# RG_Matrix_Driver.net
KiCad netlist of a schematic drawn in EAGLE
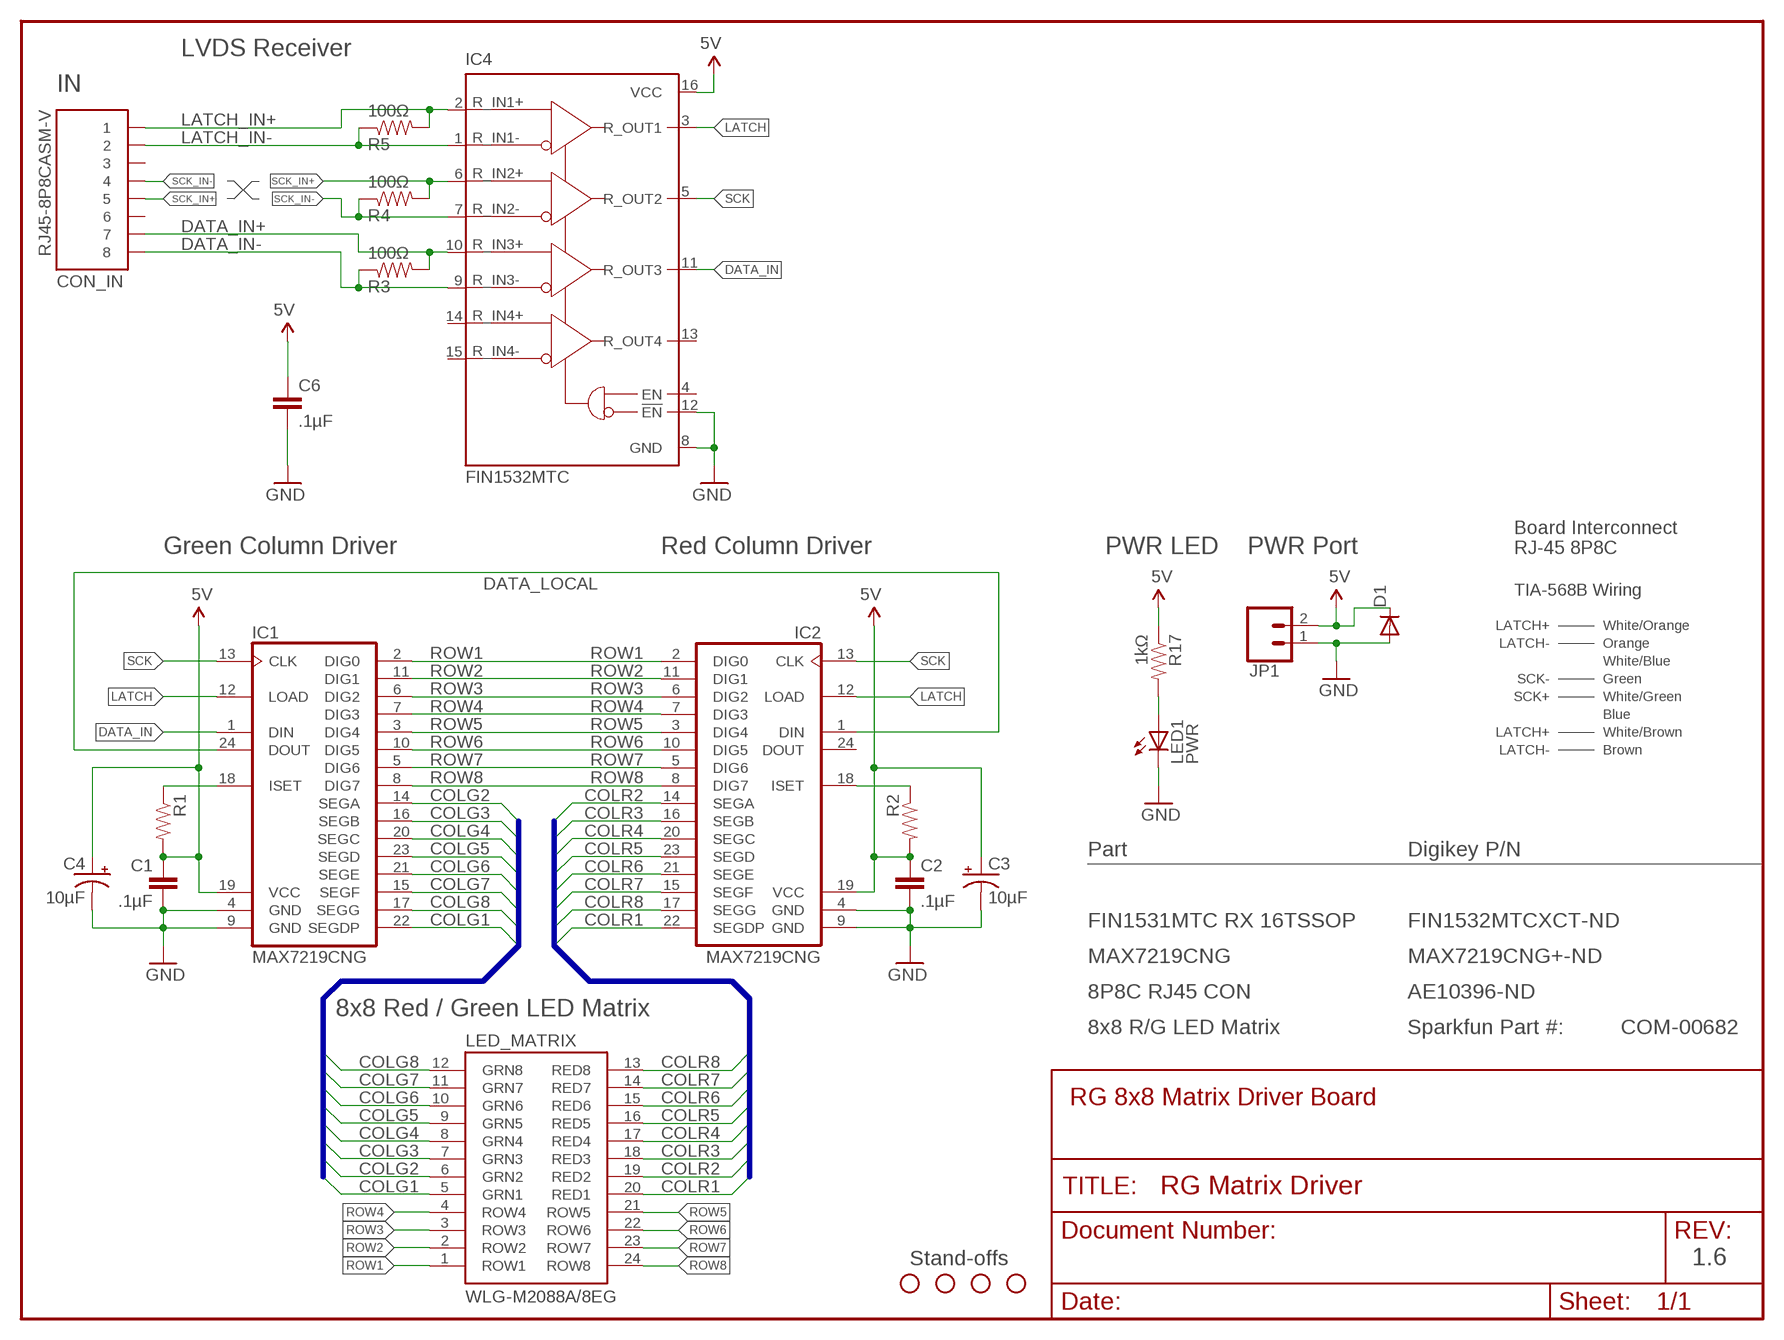
[diagram p0: schematic, sheet 1]

(export (version "E")
  (design (tool "Eeschema 10.0.6"))
  (components
    (comp (ref "C1")
      (value ".1µF")
      (footprint "eagle-import:1206")
      (libsource (lib "eagle-import") (part "CAP1206"))
    )
    (comp (ref "C2")
      (value ".1µF")
      (footprint "eagle-import:1206")
      (libsource (lib "eagle-import") (part "CAP1206"))
    )
    (comp (ref "C3")
      (value "10µF")
      (footprint "eagle-import:CPOL-RADIAL-10UF-25V")
      (libsource (lib "eagle-import") (part "CAP_POLPTH2"))
    )
    (comp (ref "C4")
      (value "10µF")
      (footprint "eagle-import:CPOL-RADIAL-10UF-25V")
      (libsource (lib "eagle-import") (part "CAP_POLPTH2"))
    )
    (comp (ref "C6")
      (value ".1µF")
      (footprint "eagle-import:1206")
      (libsource (lib "eagle-import") (part "CAP1206"))
    )
    (comp (ref "CON_IN")
      (value "RJ45-8P8CASM-V")
      (footprint "eagle-import:RJ45-8P8C-ASM")
      (libsource (lib "eagle-import") (part "RJ45-8P8CASM-V"))
    )
    (comp (ref "D1")
      (value "DIODEPTH")
      (footprint "eagle-import:DIODE-1N4001")
      (libsource (lib "eagle-import") (part "DIODEPTH"))
    )
    (comp (ref "IC1")
      (value "MAX7219CNG")
      (footprint "eagle-import:DIL24-3")
      (fields (field (name "MF") "MAXIM"))
      (libsource (lib "eagle-import") (part "MAX7219CNG"))
    )
    (comp (ref "IC2")
      (value "MAX7219CNG")
      (footprint "eagle-import:DIL24-3")
      (fields (field (name "MF") "MAXIM"))
      (libsource (lib "eagle-import") (part "MAX7219CNG"))
    )
    (comp (ref "IC4")
      (value "FIN1532MTC")
      (footprint "eagle-import:TSSOP-16")
      (libsource (lib "eagle-import") (part "FIN1532MTC"))
    )
    (comp (ref "JP1")
      (value "PWR")
      (footprint "eagle-import:1X02_PC_SMD")
      (libsource (lib "eagle-import") (part "M02"))
    )
    (comp (ref "JP3")
      (value "STAND-OFF")
      (footprint "eagle-import:STAND-OFF")
      (libsource (lib "eagle-import") (part "STAND-OFF"))
    )
    (comp (ref "JP4")
      (value "STAND-OFF")
      (footprint "eagle-import:STAND-OFF")
      (libsource (lib "eagle-import") (part "STAND-OFF"))
    )
    (comp (ref "JP5")
      (value "STAND-OFF")
      (footprint "eagle-import:STAND-OFF")
      (libsource (lib "eagle-import") (part "STAND-OFF"))
    )
    (comp (ref "JP6")
      (value "STAND-OFF")
      (footprint "eagle-import:STAND-OFF")
      (libsource (lib "eagle-import") (part "STAND-OFF"))
    )
    (comp (ref "LED1")
      (value "PWR")
      (footprint "eagle-import:LED-1206")
      (libsource (lib "eagle-import") (part "LED1206"))
    )
    (comp (ref "LED_MATRIX")
      (value "WLG-M2088A/8EG")
      (footprint "eagle-import:WLG-M2088A_8EG")
      (libsource (lib "eagle-import") (part "WLG-M2088A/8EG"))
    )
    (comp (ref "R1")
      (value "RESISTOR1206")
      (footprint "eagle-import:1206")
      (libsource (lib "eagle-import") (part "SparkFun-Resistors_RESISTOR1206"))
    )
    (comp (ref "R2")
      (value "RESISTOR1206")
      (footprint "eagle-import:1206")
      (libsource (lib "eagle-import") (part "SparkFun-Resistors_RESISTOR1206"))
    )
    (comp (ref "R3")
      (value "100Ω")
      (footprint "eagle-import:1206")
      (libsource (lib "eagle-import") (part "SparkFun-Resistors_RESISTOR1206"))
    )
    (comp (ref "R4")
      (value "100Ω")
      (footprint "eagle-import:1206")
      (libsource (lib "eagle-import") (part "SparkFun-Resistors_RESISTOR1206"))
    )
    (comp (ref "R5")
      (value "100Ω")
      (footprint "eagle-import:1206")
      (libsource (lib "eagle-import") (part "SparkFun-Resistors_RESISTOR1206"))
    )
    (comp (ref "R17")
      (value "1kΩ")
      (footprint "eagle-import:1206")
      (libsource (lib "eagle-import") (part "RESISTOR1206"))
    )
  )
  (nets
    (net (code "1") (name "/COLG1") (class "Default")
      (node (ref "IC1") (pin "22") (pinfunction "SEGDP_22") (pintype "output"))
      (node (ref "LED_MATRIX") (pin "5") (pinfunction "GRN1_5") (pintype "bidirectional"))
    )
    (net (code "2") (name "/COLG2") (class "Default")
      (node (ref "IC1") (pin "14") (pinfunction "SEGA_14") (pintype "output"))
      (node (ref "LED_MATRIX") (pin "6") (pinfunction "GRN2_6") (pintype "bidirectional"))
    )
    (net (code "3") (name "/COLG3") (class "Default")
      (node (ref "IC1") (pin "16") (pinfunction "SEGB_16") (pintype "output"))
      (node (ref "LED_MATRIX") (pin "7") (pinfunction "GRN3_7") (pintype "bidirectional"))
    )
    (net (code "4") (name "/COLG4") (class "Default")
      (node (ref "IC1") (pin "20") (pinfunction "SEGC_20") (pintype "output"))
      (node (ref "LED_MATRIX") (pin "8") (pinfunction "GRN4_8") (pintype "bidirectional"))
    )
    (net (code "5") (name "/COLG5") (class "Default")
      (node (ref "IC1") (pin "23") (pinfunction "SEGD_23") (pintype "output"))
      (node (ref "LED_MATRIX") (pin "9") (pinfunction "GRN5_9") (pintype "bidirectional"))
    )
    (net (code "6") (name "/COLG6") (class "Default")
      (node (ref "IC1") (pin "21") (pinfunction "SEGE_21") (pintype "output"))
      (node (ref "LED_MATRIX") (pin "10") (pinfunction "GRN6_10") (pintype "bidirectional"))
    )
    (net (code "7") (name "/COLG7") (class "Default")
      (node (ref "IC1") (pin "15") (pinfunction "SEGF_15") (pintype "output"))
      (node (ref "LED_MATRIX") (pin "11") (pinfunction "GRN7_11") (pintype "bidirectional"))
    )
    (net (code "8") (name "/COLG8") (class "Default")
      (node (ref "IC1") (pin "17") (pinfunction "SEGG_17") (pintype "output"))
      (node (ref "LED_MATRIX") (pin "12") (pinfunction "GRN8_12") (pintype "bidirectional"))
    )
    (net (code "9") (name "/COLR1") (class "Default")
      (node (ref "IC2") (pin "22") (pinfunction "SEGDP_22") (pintype "output"))
      (node (ref "LED_MATRIX") (pin "20") (pinfunction "RED1_20") (pintype "bidirectional"))
    )
    (net (code "10") (name "/COLR2") (class "Default")
      (node (ref "IC2") (pin "14") (pinfunction "SEGA_14") (pintype "output"))
      (node (ref "LED_MATRIX") (pin "19") (pinfunction "RED2_19") (pintype "bidirectional"))
    )
    (net (code "11") (name "/COLR3") (class "Default")
      (node (ref "IC2") (pin "16") (pinfunction "SEGB_16") (pintype "output"))
      (node (ref "LED_MATRIX") (pin "18") (pinfunction "RED3_18") (pintype "bidirectional"))
    )
    (net (code "12") (name "/COLR4") (class "Default")
      (node (ref "IC2") (pin "20") (pinfunction "SEGC_20") (pintype "output"))
      (node (ref "LED_MATRIX") (pin "17") (pinfunction "RED4_17") (pintype "bidirectional"))
    )
    (net (code "13") (name "/COLR5") (class "Default")
      (node (ref "IC2") (pin "23") (pinfunction "SEGD_23") (pintype "output"))
      (node (ref "LED_MATRIX") (pin "16") (pinfunction "RED5_16") (pintype "bidirectional"))
    )
    (net (code "14") (name "/COLR6") (class "Default")
      (node (ref "IC2") (pin "21") (pinfunction "SEGE_21") (pintype "output"))
      (node (ref "LED_MATRIX") (pin "15") (pinfunction "RED6_15") (pintype "bidirectional"))
    )
    (net (code "15") (name "/COLR7") (class "Default")
      (node (ref "IC2") (pin "15") (pinfunction "SEGF_15") (pintype "output"))
      (node (ref "LED_MATRIX") (pin "14") (pinfunction "RED7_14") (pintype "bidirectional"))
    )
    (net (code "16") (name "/COLR8") (class "Default")
      (node (ref "IC2") (pin "17") (pinfunction "SEGG_17") (pintype "output"))
      (node (ref "LED_MATRIX") (pin "13") (pinfunction "RED8_13") (pintype "bidirectional"))
    )
    (net (code "17") (name "/DATA_IN+") (class "Default")
      (node (ref "CON_IN") (pin "7") (pinfunction "7_7") (pintype "bidirectional"))
      (node (ref "IC4") (pin "10") (pinfunction "R_IN3+_10") (pintype "output"))
      (node (ref "R3") (pin "2") (pinfunction "2_2") (pintype "passive"))
    )
    (net (code "18") (name "/DATA_IN-") (class "Default")
      (node (ref "CON_IN") (pin "8") (pinfunction "8_8") (pintype "bidirectional"))
      (node (ref "IC4") (pin "9") (pinfunction "R_IN3-_9") (pintype "output"))
      (node (ref "R3") (pin "1") (pinfunction "1_1") (pintype "passive"))
    )
    (net (code "19") (name "/DATA_LOCAL") (class "Default")
      (node (ref "IC1") (pin "24") (pinfunction "DOUT_24") (pintype "output"))
      (node (ref "IC2") (pin "1") (pinfunction "DIN_1") (pintype "input"))
    )
    (net (code "20") (name "/LATCH_IN+") (class "Default")
      (node (ref "CON_IN") (pin "1") (pinfunction "1_1") (pintype "bidirectional"))
      (node (ref "IC4") (pin "2") (pinfunction "R_IN1+_2") (pintype "output"))
      (node (ref "R5") (pin "2") (pinfunction "2_2") (pintype "passive"))
    )
    (net (code "21") (name "/LATCH_IN-") (class "Default")
      (node (ref "CON_IN") (pin "2") (pinfunction "2_2") (pintype "bidirectional"))
      (node (ref "IC4") (pin "1") (pinfunction "R_IN1-_1") (pintype "output"))
      (node (ref "R5") (pin "1") (pinfunction "1_1") (pintype "passive"))
    )
    (net (code "22") (name "5V") (class "Default")
      (node (ref "C1") (pin "1") (pinfunction "1_1") (pintype "passive"))
      (node (ref "C2") (pin "1") (pinfunction "1_1") (pintype "passive"))
      (node (ref "C3") (pin "1") (pinfunction "+_1") (pintype "passive"))
      (node (ref "C4") (pin "1") (pinfunction "+_1") (pintype "passive"))
      (node (ref "C6") (pin "1") (pinfunction "1_1") (pintype "passive"))
      (node (ref "D1") (pin "C") (pinfunction "C_C") (pintype "passive"))
      (node (ref "IC1") (pin "19") (pinfunction "VCC_19") (pintype "power_in"))
      (node (ref "IC2") (pin "19") (pinfunction "VCC_19") (pintype "power_in"))
      (node (ref "IC4") (pin "16") (pinfunction "VCC_16") (pintype "power_in"))
      (node (ref "JP1") (pin "2") (pinfunction "2_2") (pintype "passive"))
      (node (ref "R1") (pin "2") (pinfunction "2_2") (pintype "passive"))
      (node (ref "R17") (pin "1") (pinfunction "1_1") (pintype "passive"))
      (node (ref "R2") (pin "2") (pinfunction "2_2") (pintype "passive"))
    )
    (net (code "23") (name "DATA_IN") (class "Default")
      (node (ref "IC1") (pin "1") (pinfunction "DIN_1") (pintype "input"))
      (node (ref "IC4") (pin "11") (pinfunction "R_OUT3_11") (pintype "output"))
    )
    (net (code "24") (name "GND") (class "Default")
      (node (ref "C1") (pin "2") (pinfunction "2_2") (pintype "passive"))
      (node (ref "C2") (pin "2") (pinfunction "2_2") (pintype "passive"))
      (node (ref "C3") (pin "2") (pinfunction "-_2") (pintype "passive"))
      (node (ref "C4") (pin "2") (pinfunction "-_2") (pintype "passive"))
      (node (ref "C6") (pin "2") (pinfunction "2_2") (pintype "passive"))
      (node (ref "D1") (pin "A") (pinfunction "A_A") (pintype "passive"))
      (node (ref "IC1") (pin "4") (pinfunction "GND_4") (pintype "power_in"))
      (node (ref "IC1") (pin "9") (pinfunction "GND_9") (pintype "power_in"))
      (node (ref "IC2") (pin "4") (pinfunction "GND_4") (pintype "power_in"))
      (node (ref "IC2") (pin "9") (pinfunction "GND_9") (pintype "power_in"))
      (node (ref "IC4") (pin "12") (pinfunction "~{EN}_12") (pintype "input"))
      (node (ref "IC4") (pin "8") (pinfunction "GND_8") (pintype "power_in"))
      (node (ref "JP1") (pin "1") (pinfunction "1_1") (pintype "passive"))
      (node (ref "LED1") (pin "C") (pinfunction "C_C") (pintype "passive"))
    )
    (net (code "25") (name "LATCH") (class "Default")
      (node (ref "IC1") (pin "12") (pinfunction "LOAD_12") (pintype "input"))
      (node (ref "IC2") (pin "12") (pinfunction "LOAD_12") (pintype "input"))
      (node (ref "IC4") (pin "3") (pinfunction "R_OUT1_3") (pintype "output"))
    )
    (net (code "26") (name "Net-(IC1-ISET)") (class "Default")
      (node (ref "IC1") (pin "18") (pinfunction "ISET_18") (pintype "input"))
      (node (ref "R1") (pin "1") (pinfunction "1_1") (pintype "passive"))
    )
    (net (code "27") (name "Net-(IC2-ISET)") (class "Default")
      (node (ref "IC2") (pin "18") (pinfunction "ISET_18") (pintype "input"))
      (node (ref "R2") (pin "1") (pinfunction "1_1") (pintype "passive"))
    )
    (net (code "28") (name "Net-(LED1-PadA)") (class "Default")
      (node (ref "LED1") (pin "A") (pinfunction "A_A") (pintype "passive"))
      (node (ref "R17") (pin "2") (pinfunction "2_2") (pintype "passive"))
    )
    (net (code "29") (name "ROW1") (class "Default")
      (node (ref "IC1") (pin "2") (pinfunction "DIG0_2") (pintype "output"))
      (node (ref "IC2") (pin "2") (pinfunction "DIG0_2") (pintype "output"))
      (node (ref "LED_MATRIX") (pin "1") (pinfunction "ROW1_1") (pintype "bidirectional"))
    )
    (net (code "30") (name "ROW2") (class "Default")
      (node (ref "IC1") (pin "11") (pinfunction "DIG1_11") (pintype "output"))
      (node (ref "IC2") (pin "11") (pinfunction "DIG1_11") (pintype "output"))
      (node (ref "LED_MATRIX") (pin "2") (pinfunction "ROW2_2") (pintype "bidirectional"))
    )
    (net (code "31") (name "ROW3") (class "Default")
      (node (ref "IC1") (pin "6") (pinfunction "DIG2_6") (pintype "output"))
      (node (ref "IC2") (pin "6") (pinfunction "DIG2_6") (pintype "output"))
      (node (ref "LED_MATRIX") (pin "3") (pinfunction "ROW3_3") (pintype "bidirectional"))
    )
    (net (code "32") (name "ROW4") (class "Default")
      (node (ref "IC1") (pin "7") (pinfunction "DIG3_7") (pintype "output"))
      (node (ref "IC2") (pin "7") (pinfunction "DIG3_7") (pintype "output"))
      (node (ref "LED_MATRIX") (pin "4") (pinfunction "ROW4_4") (pintype "bidirectional"))
    )
    (net (code "33") (name "ROW5") (class "Default")
      (node (ref "IC1") (pin "3") (pinfunction "DIG4_3") (pintype "output"))
      (node (ref "IC2") (pin "3") (pinfunction "DIG4_3") (pintype "output"))
      (node (ref "LED_MATRIX") (pin "21") (pinfunction "ROW5_21") (pintype "bidirectional"))
    )
    (net (code "34") (name "ROW6") (class "Default")
      (node (ref "IC1") (pin "10") (pinfunction "DIG5_10") (pintype "output"))
      (node (ref "IC2") (pin "10") (pinfunction "DIG5_10") (pintype "output"))
      (node (ref "LED_MATRIX") (pin "22") (pinfunction "ROW6_22") (pintype "bidirectional"))
    )
    (net (code "35") (name "ROW7") (class "Default")
      (node (ref "IC1") (pin "5") (pinfunction "DIG6_5") (pintype "output"))
      (node (ref "IC2") (pin "5") (pinfunction "DIG6_5") (pintype "output"))
      (node (ref "LED_MATRIX") (pin "23") (pinfunction "ROW7_23") (pintype "bidirectional"))
    )
    (net (code "36") (name "ROW8") (class "Default")
      (node (ref "IC1") (pin "8") (pinfunction "DIG7_8") (pintype "output"))
      (node (ref "IC2") (pin "8") (pinfunction "DIG7_8") (pintype "output"))
      (node (ref "LED_MATRIX") (pin "24") (pinfunction "ROW8_24") (pintype "bidirectional"))
    )
    (net (code "37") (name "SCK") (class "Default")
      (node (ref "IC1") (pin "13") (pinfunction "CLK_13") (pintype "input"))
      (node (ref "IC2") (pin "13") (pinfunction "CLK_13") (pintype "input"))
      (node (ref "IC4") (pin "5") (pinfunction "R_OUT2_5") (pintype "output"))
    )
    (net (code "38") (name "SCK_IN+") (class "Default")
      (node (ref "CON_IN") (pin "5") (pinfunction "5_5") (pintype "bidirectional"))
      (node (ref "IC4") (pin "6") (pinfunction "R_IN2+_6") (pintype "output"))
      (node (ref "R4") (pin "2") (pinfunction "2_2") (pintype "passive"))
    )
    (net (code "39") (name "SCK_IN-") (class "Default")
      (node (ref "CON_IN") (pin "4") (pinfunction "4_4") (pintype "bidirectional"))
      (node (ref "IC4") (pin "7") (pinfunction "R_IN2-_7") (pintype "output"))
      (node (ref "R4") (pin "1") (pinfunction "1_1") (pintype "passive"))
    )
    (net (code "40") (name "unconnected-(CON_IN-Pad3)") (class "Default")
      (node (ref "CON_IN") (pin "3") (pinfunction "3_3") (pintype "bidirectional"))
    )
    (net (code "41") (name "unconnected-(CON_IN-Pad6)") (class "Default")
      (node (ref "CON_IN") (pin "6") (pinfunction "6_6") (pintype "bidirectional"))
    )
    (net (code "42") (name "unconnected-(IC2-DOUT-Pad24)") (class "Default")
      (node (ref "IC2") (pin "24") (pinfunction "DOUT_24") (pintype "output"))
    )
    (net (code "43") (name "unconnected-(IC4-EN-Pad4)") (class "Default")
      (node (ref "IC4") (pin "4") (pinfunction "EN_4") (pintype "input"))
    )
    (net (code "44") (name "unconnected-(IC4-R_OUT4+-Pad14)") (class "Default")
      (node (ref "IC4") (pin "14") (pinfunction "R_OUT4+_14") (pintype "output"))
    )
    (net (code "45") (name "unconnected-(IC4-R_OUT4--Pad15)") (class "Default")
      (node (ref "IC4") (pin "15") (pinfunction "R_OUT4-_15") (pintype "output"))
    )
    (net (code "46") (name "unconnected-(IC4-R_OUT4-Pad13)") (class "Default")
      (node (ref "IC4") (pin "13") (pinfunction "R_OUT4_13") (pintype "output"))
    )
  )
)
